# BumpSensors.net
KiCad netlist of a schematic drawn in Altium Designer
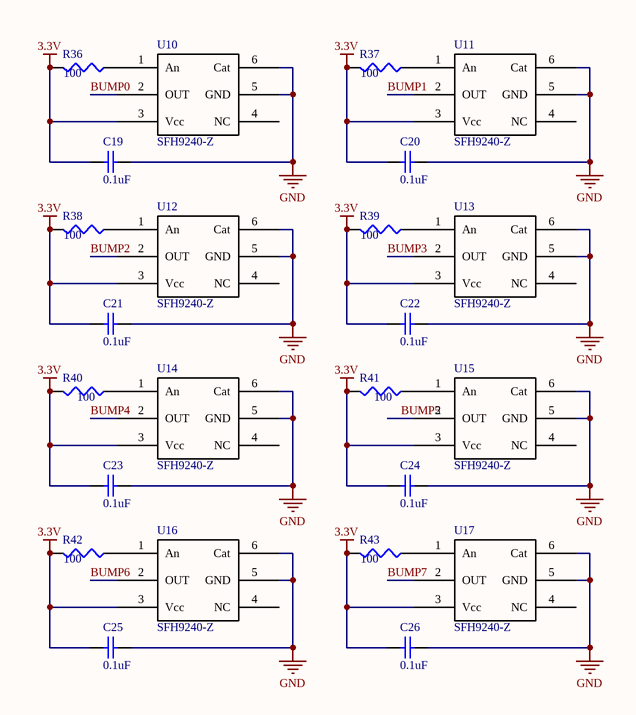
[diagram p0: BumpSensors.SchDoc]

(export (version "E")
  (design (tool "Eeschema 10.0.6"))
  (components
    (comp (ref "C19")
      (value "0.1uF")
      (footprint "CAPC1005L")
      (description "Capacitor (Semiconductor SIM Model)")
      (fields (field (name "Comment") "Cap Semi") (field (name "PUBLISHER") "Altium Limited"))
      (libsource (lib "Miscellaneous Devices") (part "Cap Semi"))
    )
    (comp (ref "C20")
      (value "0.1uF")
      (footprint "CAPC1005L")
      (description "Capacitor (Semiconductor SIM Model)")
      (fields (field (name "Comment") "Cap Semi") (field (name "PUBLISHER") "Altium Limited"))
      (libsource (lib "Miscellaneous Devices") (part "Cap Semi"))
    )
    (comp (ref "C21")
      (value "0.1uF")
      (footprint "CAPC1005L")
      (description "Capacitor (Semiconductor SIM Model)")
      (fields (field (name "Comment") "Cap Semi") (field (name "PUBLISHER") "Altium Limited"))
      (libsource (lib "Miscellaneous Devices") (part "Cap Semi"))
    )
    (comp (ref "C22")
      (value "0.1uF")
      (footprint "CAPC1005L")
      (description "Capacitor (Semiconductor SIM Model)")
      (fields (field (name "Comment") "Cap Semi") (field (name "PUBLISHER") "Altium Limited"))
      (libsource (lib "Miscellaneous Devices") (part "Cap Semi"))
    )
    (comp (ref "C23")
      (value "0.1uF")
      (footprint "CAPC1005L")
      (description "Capacitor (Semiconductor SIM Model)")
      (fields (field (name "Comment") "Cap Semi") (field (name "PUBLISHER") "Altium Limited"))
      (libsource (lib "Miscellaneous Devices") (part "Cap Semi"))
    )
    (comp (ref "C24")
      (value "0.1uF")
      (footprint "CAPC1005L")
      (description "Capacitor (Semiconductor SIM Model)")
      (fields (field (name "Comment") "Cap Semi") (field (name "PUBLISHER") "Altium Limited"))
      (libsource (lib "Miscellaneous Devices") (part "Cap Semi"))
    )
    (comp (ref "C25")
      (value "0.1uF")
      (footprint "CAPC1005L")
      (description "Capacitor (Semiconductor SIM Model)")
      (fields (field (name "Comment") "Cap Semi") (field (name "PUBLISHER") "Altium Limited"))
      (libsource (lib "Miscellaneous Devices") (part "Cap Semi"))
    )
    (comp (ref "C26")
      (value "0.1uF")
      (footprint "CAPC1005L")
      (description "Capacitor (Semiconductor SIM Model)")
      (fields (field (name "Comment") "Cap Semi") (field (name "PUBLISHER") "Altium Limited"))
      (libsource (lib "Miscellaneous Devices") (part "Cap Semi"))
    )
    (comp (ref "R36")
      (value "100")
      (footprint "RESC1608L")
      (description "Resistor")
      (fields (field (name "Comment") "Res3") (field (name "PUBLISHER") "Altium Limited"))
      (libsource (lib "Miscellaneous Devices") (part "Res3"))
    )
    (comp (ref "R37")
      (value "100")
      (footprint "RESC1608L")
      (description "Resistor")
      (fields (field (name "Comment") "Res3") (field (name "PUBLISHER") "Altium Limited"))
      (libsource (lib "Miscellaneous Devices") (part "Res3"))
    )
    (comp (ref "R38")
      (value "100")
      (footprint "RESC1608L")
      (description "Resistor")
      (fields (field (name "Comment") "Res3") (field (name "PUBLISHER") "Altium Limited"))
      (libsource (lib "Miscellaneous Devices") (part "Res3"))
    )
    (comp (ref "R39")
      (value "100")
      (footprint "RESC1608L")
      (description "Resistor")
      (fields (field (name "Comment") "Res3") (field (name "PUBLISHER") "Altium Limited"))
      (libsource (lib "Miscellaneous Devices") (part "Res3"))
    )
    (comp (ref "R40")
      (value "100")
      (footprint "RESC1608L")
      (description "Resistor")
      (fields (field (name "Comment") "Res3") (field (name "PUBLISHER") "Altium Limited"))
      (libsource (lib "Miscellaneous Devices") (part "Res3"))
    )
    (comp (ref "R41")
      (value "100")
      (footprint "RESC1608L")
      (description "Resistor")
      (fields (field (name "Comment") "Res3") (field (name "PUBLISHER") "Altium Limited"))
      (libsource (lib "Miscellaneous Devices") (part "Res3"))
    )
    (comp (ref "R42")
      (value "100")
      (footprint "RESC1608L")
      (description "Resistor")
      (fields (field (name "Comment") "Res3") (field (name "PUBLISHER") "Altium Limited"))
      (libsource (lib "Miscellaneous Devices") (part "Res3"))
    )
    (comp (ref "R43")
      (value "100")
      (footprint "RESC1608L")
      (description "Resistor")
      (fields (field (name "Comment") "Res3") (field (name "PUBLISHER") "Altium Limited"))
      (libsource (lib "Miscellaneous Devices") (part "Res3"))
    )
    (comp (ref "U10")
      (value "SFH9240-Z")
      (footprint "SFH9240-Z")
      (libsource (lib "mrone") (part "SFH9240-Z"))
    )
    (comp (ref "U11")
      (value "SFH9240-Z")
      (footprint "SFH9240-Z")
      (libsource (lib "mrone") (part "SFH9240-Z"))
    )
    (comp (ref "U12")
      (value "SFH9240-Z")
      (footprint "SFH9240-Z")
      (libsource (lib "mrone") (part "SFH9240-Z"))
    )
    (comp (ref "U13")
      (value "SFH9240-Z")
      (footprint "SFH9240-Z")
      (libsource (lib "mrone") (part "SFH9240-Z"))
    )
    (comp (ref "U14")
      (value "SFH9240-Z")
      (footprint "SFH9240-Z")
      (libsource (lib "mrone") (part "SFH9240-Z"))
    )
    (comp (ref "U15")
      (value "SFH9240-Z")
      (footprint "SFH9240-Z")
      (libsource (lib "mrone") (part "SFH9240-Z"))
    )
    (comp (ref "U16")
      (value "SFH9240-Z")
      (footprint "SFH9240-Z")
      (libsource (lib "mrone") (part "SFH9240-Z"))
    )
    (comp (ref "U17")
      (value "SFH9240-Z")
      (footprint "SFH9240-Z")
      (libsource (lib "mrone") (part "SFH9240-Z"))
    )
  )
  (nets
    (net (code "1") (name "/BUMP0") (class "Default")
      (node (ref "U10") (pin "2") (pinfunction "OUT_2") (pintype "passive"))
    )
    (net (code "2") (name "/BUMP1") (class "Default")
      (node (ref "U11") (pin "2") (pinfunction "OUT_2") (pintype "passive"))
    )
    (net (code "3") (name "/BUMP2") (class "Default")
      (node (ref "U12") (pin "2") (pinfunction "OUT_2") (pintype "passive"))
    )
    (net (code "4") (name "/BUMP3") (class "Default")
      (node (ref "U13") (pin "2") (pinfunction "OUT_2") (pintype "passive"))
    )
    (net (code "5") (name "/BUMP4") (class "Default")
      (node (ref "U14") (pin "2") (pinfunction "OUT_2") (pintype "passive"))
    )
    (net (code "6") (name "/BUMP5") (class "Default")
      (node (ref "U15") (pin "2") (pinfunction "OUT_2") (pintype "passive"))
    )
    (net (code "7") (name "/BUMP6") (class "Default")
      (node (ref "U16") (pin "2") (pinfunction "OUT_2") (pintype "passive"))
    )
    (net (code "8") (name "/BUMP7") (class "Default")
      (node (ref "U17") (pin "2") (pinfunction "OUT_2") (pintype "passive"))
    )
    (net (code "9") (name "3.3V") (class "Default")
      (node (ref "C19") (pin "2") (pinfunction "2_2") (pintype "passive"))
      (node (ref "C20") (pin "2") (pinfunction "2_2") (pintype "passive"))
      (node (ref "C21") (pin "2") (pinfunction "2_2") (pintype "passive"))
      (node (ref "C22") (pin "2") (pinfunction "2_2") (pintype "passive"))
      (node (ref "C23") (pin "2") (pinfunction "2_2") (pintype "passive"))
      (node (ref "C24") (pin "2") (pinfunction "2_2") (pintype "passive"))
      (node (ref "C25") (pin "2") (pinfunction "2_2") (pintype "passive"))
      (node (ref "C26") (pin "2") (pinfunction "2_2") (pintype "passive"))
      (node (ref "R36") (pin "2") (pinfunction "2_2") (pintype "passive"))
      (node (ref "R37") (pin "2") (pinfunction "2_2") (pintype "passive"))
      (node (ref "R38") (pin "2") (pinfunction "2_2") (pintype "passive"))
      (node (ref "R39") (pin "2") (pinfunction "2_2") (pintype "passive"))
      (node (ref "R40") (pin "2") (pinfunction "2_2") (pintype "passive"))
      (node (ref "R41") (pin "2") (pinfunction "2_2") (pintype "passive"))
      (node (ref "R42") (pin "2") (pinfunction "2_2") (pintype "passive"))
      (node (ref "R43") (pin "2") (pinfunction "2_2") (pintype "passive"))
      (node (ref "U10") (pin "3") (pinfunction "Vcc_3") (pintype "passive"))
      (node (ref "U11") (pin "3") (pinfunction "Vcc_3") (pintype "passive"))
      (node (ref "U12") (pin "3") (pinfunction "Vcc_3") (pintype "passive"))
      (node (ref "U13") (pin "3") (pinfunction "Vcc_3") (pintype "passive"))
      (node (ref "U14") (pin "3") (pinfunction "Vcc_3") (pintype "passive"))
      (node (ref "U15") (pin "3") (pinfunction "Vcc_3") (pintype "passive"))
      (node (ref "U16") (pin "3") (pinfunction "Vcc_3") (pintype "passive"))
      (node (ref "U17") (pin "3") (pinfunction "Vcc_3") (pintype "passive"))
    )
    (net (code "10") (name "GND") (class "Default")
      (node (ref "C19") (pin "1") (pinfunction "1_1") (pintype "passive"))
      (node (ref "C20") (pin "1") (pinfunction "1_1") (pintype "passive"))
      (node (ref "C21") (pin "1") (pinfunction "1_1") (pintype "passive"))
      (node (ref "C22") (pin "1") (pinfunction "1_1") (pintype "passive"))
      (node (ref "C23") (pin "1") (pinfunction "1_1") (pintype "passive"))
      (node (ref "C24") (pin "1") (pinfunction "1_1") (pintype "passive"))
      (node (ref "C25") (pin "1") (pinfunction "1_1") (pintype "passive"))
      (node (ref "C26") (pin "1") (pinfunction "1_1") (pintype "passive"))
      (node (ref "U10") (pin "5") (pinfunction "GND_5") (pintype "passive"))
      (node (ref "U10") (pin "6") (pinfunction "Cat_6") (pintype "passive"))
      (node (ref "U11") (pin "5") (pinfunction "GND_5") (pintype "passive"))
      (node (ref "U11") (pin "6") (pinfunction "Cat_6") (pintype "passive"))
      (node (ref "U12") (pin "5") (pinfunction "GND_5") (pintype "passive"))
      (node (ref "U12") (pin "6") (pinfunction "Cat_6") (pintype "passive"))
      (node (ref "U13") (pin "5") (pinfunction "GND_5") (pintype "passive"))
      (node (ref "U13") (pin "6") (pinfunction "Cat_6") (pintype "passive"))
      (node (ref "U14") (pin "5") (pinfunction "GND_5") (pintype "passive"))
      (node (ref "U14") (pin "6") (pinfunction "Cat_6") (pintype "passive"))
      (node (ref "U15") (pin "5") (pinfunction "GND_5") (pintype "passive"))
      (node (ref "U15") (pin "6") (pinfunction "Cat_6") (pintype "passive"))
      (node (ref "U16") (pin "5") (pinfunction "GND_5") (pintype "passive"))
      (node (ref "U16") (pin "6") (pinfunction "Cat_6") (pintype "passive"))
      (node (ref "U17") (pin "5") (pinfunction "GND_5") (pintype "passive"))
      (node (ref "U17") (pin "6") (pinfunction "Cat_6") (pintype "passive"))
    )
    (net (code "11") (name "Net-(U10-An)") (class "Default")
      (node (ref "R36") (pin "1") (pinfunction "1_1") (pintype "passive"))
      (node (ref "U10") (pin "1") (pinfunction "An_1") (pintype "passive"))
    )
    (net (code "12") (name "Net-(U11-An)") (class "Default")
      (node (ref "R37") (pin "1") (pinfunction "1_1") (pintype "passive"))
      (node (ref "U11") (pin "1") (pinfunction "An_1") (pintype "passive"))
    )
    (net (code "13") (name "Net-(U12-An)") (class "Default")
      (node (ref "R38") (pin "1") (pinfunction "1_1") (pintype "passive"))
      (node (ref "U12") (pin "1") (pinfunction "An_1") (pintype "passive"))
    )
    (net (code "14") (name "Net-(U13-An)") (class "Default")
      (node (ref "R39") (pin "1") (pinfunction "1_1") (pintype "passive"))
      (node (ref "U13") (pin "1") (pinfunction "An_1") (pintype "passive"))
    )
    (net (code "15") (name "Net-(U14-An)") (class "Default")
      (node (ref "R40") (pin "1") (pinfunction "1_1") (pintype "passive"))
      (node (ref "U14") (pin "1") (pinfunction "An_1") (pintype "passive"))
    )
    (net (code "16") (name "Net-(U15-An)") (class "Default")
      (node (ref "R41") (pin "1") (pinfunction "1_1") (pintype "passive"))
      (node (ref "U15") (pin "1") (pinfunction "An_1") (pintype "passive"))
    )
    (net (code "17") (name "Net-(U16-An)") (class "Default")
      (node (ref "R42") (pin "1") (pinfunction "1_1") (pintype "passive"))
      (node (ref "U16") (pin "1") (pinfunction "An_1") (pintype "passive"))
    )
    (net (code "18") (name "Net-(U17-An)") (class "Default")
      (node (ref "R43") (pin "1") (pinfunction "1_1") (pintype "passive"))
      (node (ref "U17") (pin "1") (pinfunction "An_1") (pintype "passive"))
    )
    (net (code "19") (name "unconnected-(U10-NC-Pad4)") (class "Default")
      (node (ref "U10") (pin "4") (pinfunction "NC_4") (pintype "passive"))
    )
    (net (code "20") (name "unconnected-(U11-NC-Pad4)") (class "Default")
      (node (ref "U11") (pin "4") (pinfunction "NC_4") (pintype "passive"))
    )
    (net (code "21") (name "unconnected-(U12-NC-Pad4)") (class "Default")
      (node (ref "U12") (pin "4") (pinfunction "NC_4") (pintype "passive"))
    )
    (net (code "22") (name "unconnected-(U13-NC-Pad4)") (class "Default")
      (node (ref "U13") (pin "4") (pinfunction "NC_4") (pintype "passive"))
    )
    (net (code "23") (name "unconnected-(U14-NC-Pad4)") (class "Default")
      (node (ref "U14") (pin "4") (pinfunction "NC_4") (pintype "passive"))
    )
    (net (code "24") (name "unconnected-(U15-NC-Pad4)") (class "Default")
      (node (ref "U15") (pin "4") (pinfunction "NC_4") (pintype "passive"))
    )
    (net (code "25") (name "unconnected-(U16-NC-Pad4)") (class "Default")
      (node (ref "U16") (pin "4") (pinfunction "NC_4") (pintype "passive"))
    )
    (net (code "26") (name "unconnected-(U17-NC-Pad4)") (class "Default")
      (node (ref "U17") (pin "4") (pinfunction "NC_4") (pintype "passive"))
    )
  )
)
